# UV_Curing-PCB.net
KiCad netlist of a schematic drawn in EAGLE
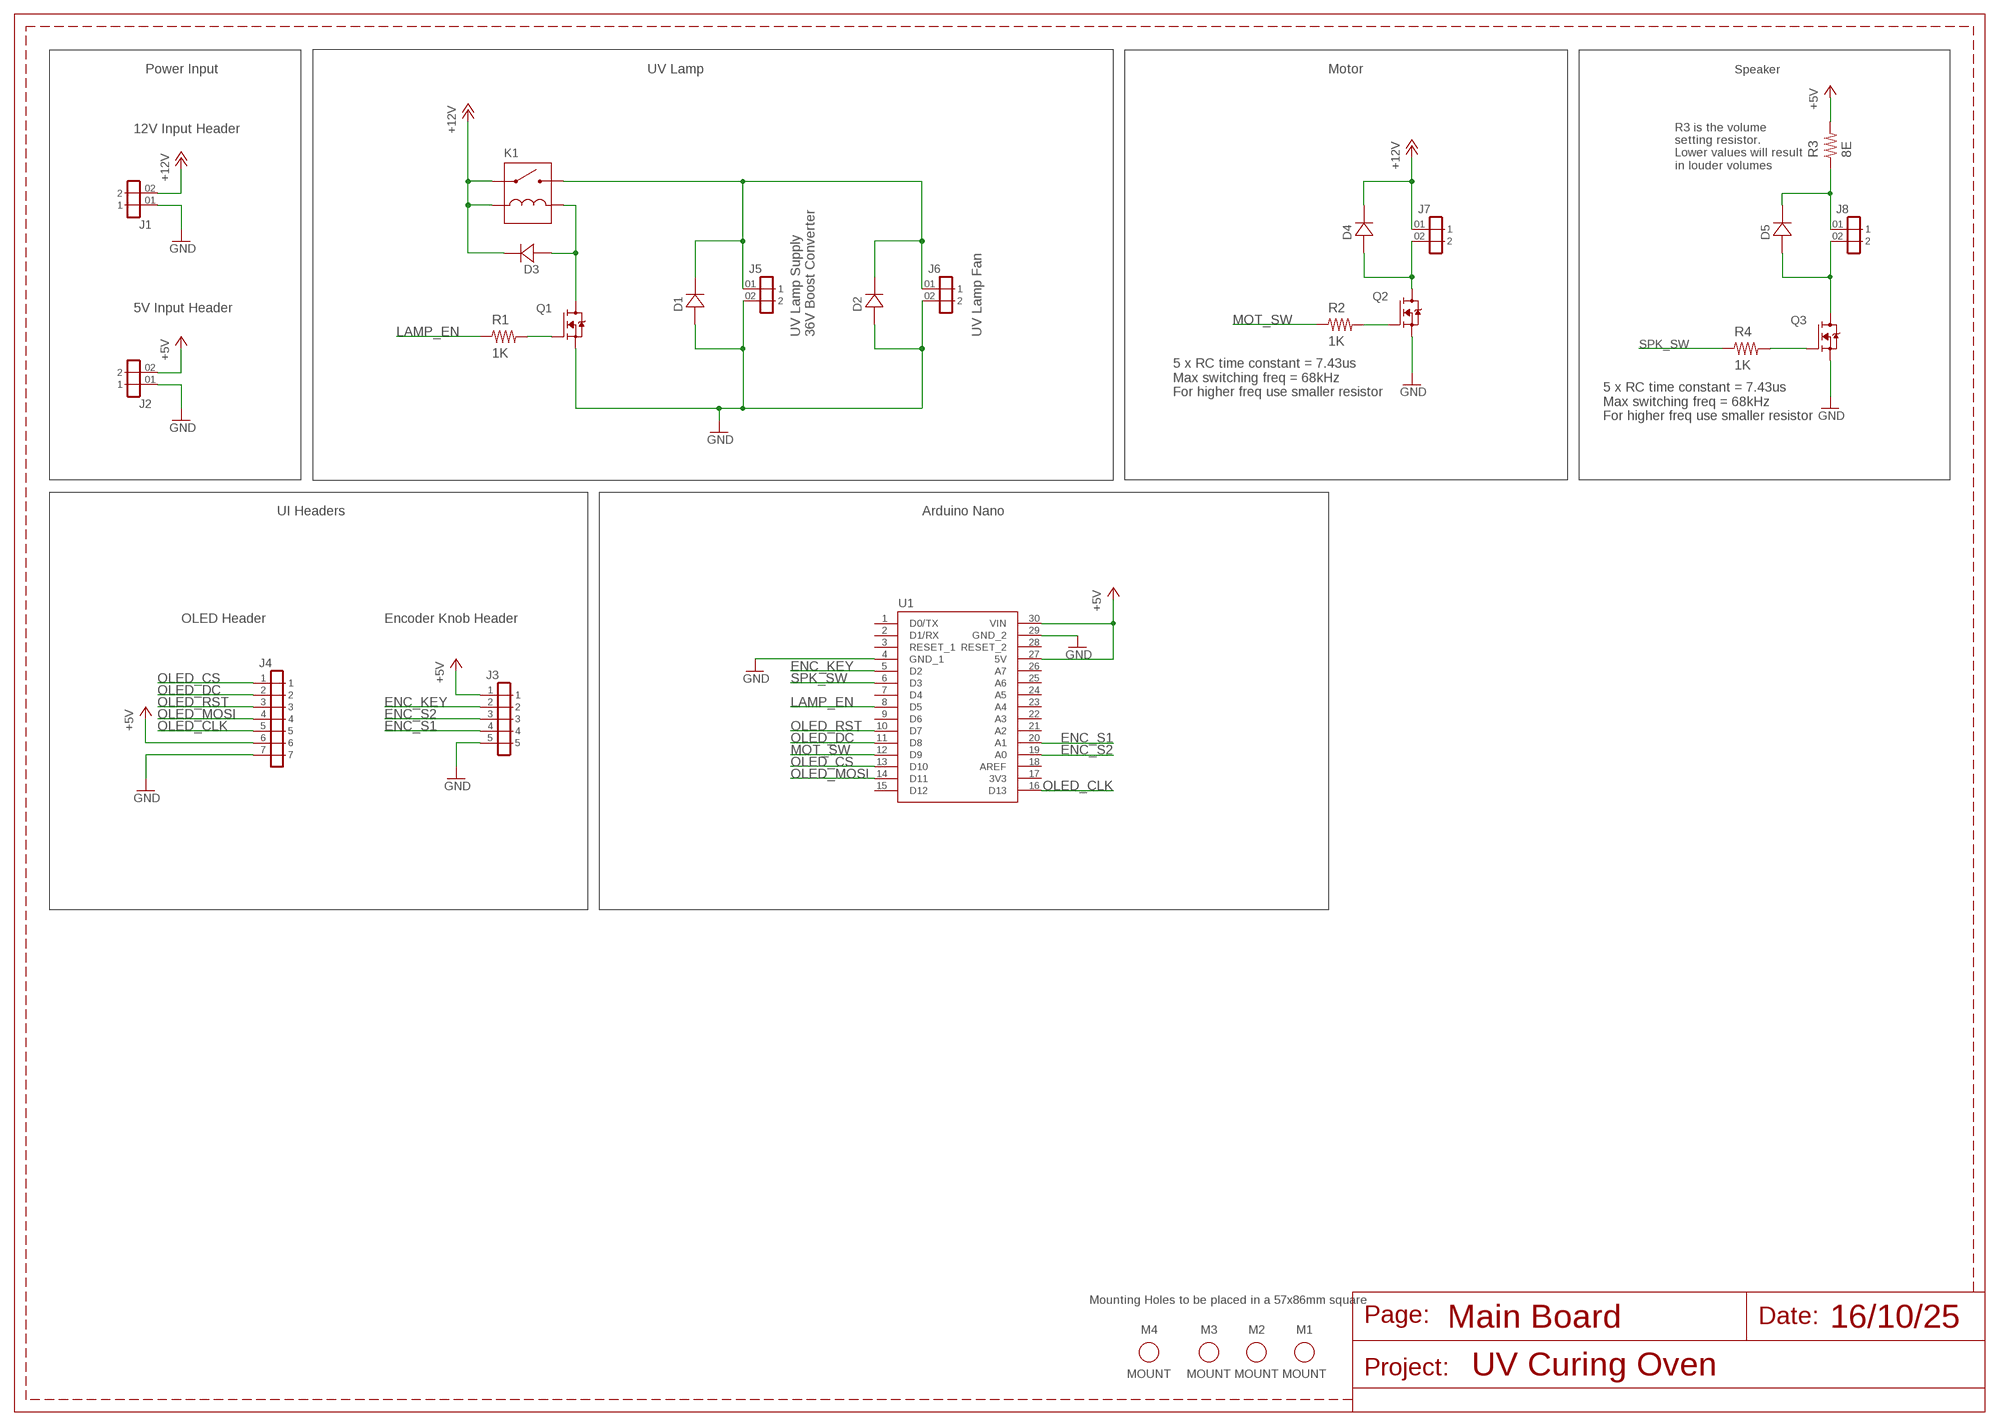
[diagram p0: schematic, sheet 1]

(export (version "E")
  (design (tool "Eeschema 10.0.6"))
  (components
    (comp (ref "D1")
      (value "400V")
      (footprint "eagle-import:DIOAD520W79L463D238")
      (fields (field (name "MF") "Diotec Semiconductor") (field (name "MP") "1N4004"))
      (libsource (lib "eagle-import") (part "DIODE-DO-41-TH"))
    )
    (comp (ref "D2")
      (value "400V")
      (footprint "eagle-import:DIOAD520W79L463D238")
      (fields (field (name "MF") "Diotec Semiconductor") (field (name "MP") "1N4004"))
      (libsource (lib "eagle-import") (part "DIODE-DO-41-TH"))
    )
    (comp (ref "D3")
      (value "400V")
      (footprint "eagle-import:DIOAD520W79L463D238")
      (fields (field (name "MF") "Diotec Semiconductor") (field (name "MP") "1N4004"))
      (libsource (lib "eagle-import") (part "DIODE-DO-41-TH"))
    )
    (comp (ref "D4")
      (value "400V")
      (footprint "eagle-import:DIOAD520W79L463D238")
      (fields (field (name "MF") "Diotec Semiconductor") (field (name "MP") "1N4004"))
      (libsource (lib "eagle-import") (part "DIODE-DO-41-TH"))
    )
    (comp (ref "D5")
      (value "400V")
      (footprint "eagle-import:DIOAD520W79L463D238")
      (fields (field (name "MF") "Diotec Semiconductor") (field (name "MP") "1N4004"))
      (libsource (lib "eagle-import") (part "DIODE-DO-41-TH"))
    )
    (comp (ref "J1")
      (value "PINHEADER-2POS-2.54MM")
      (footprint "eagle-import:254-1X02-PIN")
      (fields (field (name "MF") "Wurth Electronics") (field (name "MP") "61300211121"))
      (libsource (lib "eagle-import") (part "PINHEADER-2POS-2.54MM"))
    )
    (comp (ref "J2")
      (value "PINHEADER-2POS-2.54MM")
      (footprint "eagle-import:254-1X02-PIN")
      (fields (field (name "MF") "Wurth Electronics") (field (name "MP") "61300211121"))
      (libsource (lib "eagle-import") (part "PINHEADER-2POS-2.54MM"))
    )
    (comp (ref "J3")
      (value "PINHEADER-5POS-2.54MM")
      (footprint "eagle-import:254-1X05-PIN")
      (fields (field (name "MF") "Wurth Electronics") (field (name "MP") "61300511121"))
      (libsource (lib "eagle-import") (part "PINHEADER-5POS-2.54MM"))
    )
    (comp (ref "J4")
      (value "PINHEADER-7POS-2.54MM")
      (footprint "eagle-import:254-1X07-PIN")
      (fields (field (name "MF") "Wurth Elektronik") (field (name "MP") "61300711121"))
      (libsource (lib "eagle-import") (part "PINHEADER-7POS-2.54MM"))
    )
    (comp (ref "J5")
      (value "PINHEADER-2POS-2.54MM")
      (footprint "eagle-import:254-1X02-PIN")
      (fields (field (name "MF") "Wurth Electronics") (field (name "MP") "61300211121"))
      (libsource (lib "eagle-import") (part "PINHEADER-2POS-2.54MM"))
    )
    (comp (ref "J6")
      (value "PINHEADER-2POS-2.54MM")
      (footprint "eagle-import:254-1X02-PIN")
      (fields (field (name "MF") "Wurth Electronics") (field (name "MP") "61300211121"))
      (libsource (lib "eagle-import") (part "PINHEADER-2POS-2.54MM"))
    )
    (comp (ref "J7")
      (value "PINHEADER-2POS-2.54MM")
      (footprint "eagle-import:254-1X02-PIN")
      (fields (field (name "MF") "Wurth Electronics") (field (name "MP") "61300211121"))
      (libsource (lib "eagle-import") (part "PINHEADER-2POS-2.54MM"))
    )
    (comp (ref "J8")
      (value "PINHEADER-2POS-2.54MM")
      (footprint "eagle-import:254-1X02-PIN")
      (fields (field (name "MF") "Wurth Electronics") (field (name "MP") "61300211121"))
      (libsource (lib "eagle-import") (part "PINHEADER-2POS-2.54MM"))
    )
    (comp (ref "K1")
      (value "25V")
      (footprint "eagle-import:JY25HK505")
      (fields (field (name "MF") "FUJITSU") (field (name "MP") "JY-25H-K-505"))
      (libsource (lib "eagle-import") (part "RELAY-NO"))
    )
    (comp (ref "M1")
      (value "MOUNTING_HOLE")
      (footprint "eagle-import:M4_NP_MOUNTING_HOLE")
      (libsource (lib "eagle-import") (part "MOUNTING_HOLE"))
    )
    (comp (ref "M2")
      (value "MOUNTING_HOLE")
      (footprint "eagle-import:M4_NP_MOUNTING_HOLE")
      (libsource (lib "eagle-import") (part "MOUNTING_HOLE"))
    )
    (comp (ref "M3")
      (value "MOUNTING_HOLE")
      (footprint "eagle-import:M4_NP_MOUNTING_HOLE")
      (libsource (lib "eagle-import") (part "MOUNTING_HOLE"))
    )
    (comp (ref "M4")
      (value "MOUNTING_HOLE")
      (footprint "eagle-import:M4_NP_MOUNTING_HOLE")
      (libsource (lib "eagle-import") (part "MOUNTING_HOLE"))
    )
    (comp (ref "Q1")
      (value "55V")
      (footprint "eagle-import:TO254P1016X419X2286-3")
      (fields (field (name "MF") "Infineon") (field (name "MP") "IRFZ44NPBF"))
      (libsource (lib "eagle-import") (part "MOSFET-NCH-TO-220AB-TH"))
    )
    (comp (ref "Q2")
      (value "55V")
      (footprint "eagle-import:TO254P1016X419X2286-3")
      (fields (field (name "MF") "Infineon") (field (name "MP") "IRFZ44NPBF"))
      (libsource (lib "eagle-import") (part "MOSFET-NCH-TO-220AB-TH"))
    )
    (comp (ref "Q3")
      (value "55V")
      (footprint "eagle-import:TO254P1016X419X2286-3")
      (fields (field (name "MF") "Infineon") (field (name "MP") "IRFZ44NPBF"))
      (libsource (lib "eagle-import") (part "MOSFET-NCH-TO-220AB-TH"))
    )
    (comp (ref "R1")
      (value "1K")
      (footprint "eagle-import:RES-THRU")
      (fields (field (name "MF") "Yageo") (field (name "MP") "MFR-25FBF52-1K"))
      (libsource (lib "eagle-import") (part "MFR-25FBF52-1K"))
    )
    (comp (ref "R2")
      (value "1K")
      (footprint "eagle-import:RES-THRU")
      (fields (field (name "MF") "Yageo") (field (name "MP") "MFR-25FBF52-1K"))
      (libsource (lib "eagle-import") (part "MFR-25FBF52-1K"))
    )
    (comp (ref "R3")
      (value "8E")
      (footprint "eagle-import:RES-THRU")
      (fields (field (name "MF") "Yageo") (field (name "MP") "MFR-25FBF52-1K"))
      (libsource (lib "eagle-import") (part "MFR-25FBF52-1K"))
    )
    (comp (ref "R4")
      (value "1K")
      (footprint "eagle-import:RES-THRU")
      (fields (field (name "MF") "Yageo") (field (name "MP") "MFR-25FBF52-1K"))
      (libsource (lib "eagle-import") (part "MFR-25FBF52-1K"))
    )
    (comp (ref "U1")
      (value "A000005")
      (footprint "eagle-import:MODULE_A000005")
      (fields (field (name "MF") "Arduino"))
      (libsource (lib "eagle-import") (part "A000005"))
    )
  )
  (nets
    (net (code "1") (name "+5V") (class "Default")
      (node (ref "J2") (pin "02") (pinfunction "2_02") (pintype "passive"))
      (node (ref "J3") (pin "1") (pinfunction "1_1") (pintype "bidirectional"))
      (node (ref "J4") (pin "6") (pinfunction "6_6") (pintype "bidirectional"))
      (node (ref "R3") (pin "2") (pinfunction "2_2") (pintype "passive"))
      (node (ref "U1") (pin "27") (pinfunction "5V_27") (pintype "power_in"))
      (node (ref "U1") (pin "30") (pinfunction "VIN_30") (pintype "power_in"))
    )
    (net (code "2") (name "+12V") (class "Default")
      (node (ref "D3") (pin "C") (pinfunction "C_C") (pintype "passive"))
      (node (ref "D4") (pin "C") (pinfunction "C_C") (pintype "passive"))
      (node (ref "J1") (pin "02") (pinfunction "2_02") (pintype "passive"))
      (node (ref "J7") (pin "01") (pinfunction "1_01") (pintype "passive"))
      (node (ref "K1") (pin "16") (pinfunction "COM_16") (pintype "bidirectional"))
      (node (ref "K1") (pin "8") (pinfunction "COIL_1_8") (pintype "bidirectional"))
    )
    (net (code "3") (name "/3V3") (class "Default")
      (node (ref "U1") (pin "17") (pinfunction "3V3_17") (pintype "power_in"))
    )
    (net (code "4") (name "/ENC_KEY") (class "Default")
      (node (ref "J3") (pin "2") (pinfunction "2_2") (pintype "bidirectional"))
      (node (ref "U1") (pin "5") (pinfunction "D2_5") (pintype "bidirectional"))
    )
    (net (code "5") (name "/ENC_S1") (class "Default")
      (node (ref "J3") (pin "4") (pinfunction "4_4") (pintype "bidirectional"))
      (node (ref "U1") (pin "20") (pinfunction "A1_20") (pintype "input"))
    )
    (net (code "6") (name "/ENC_S2") (class "Default")
      (node (ref "J3") (pin "3") (pinfunction "3_3") (pintype "bidirectional"))
      (node (ref "U1") (pin "19") (pinfunction "A0_19") (pintype "input"))
    )
    (net (code "7") (name "/LAMP_EN") (class "Default")
      (node (ref "R1") (pin "1") (pinfunction "1_1") (pintype "passive"))
      (node (ref "U1") (pin "8") (pinfunction "D5_8") (pintype "bidirectional"))
    )
    (net (code "8") (name "/MOT_SW") (class "Default")
      (node (ref "R2") (pin "1") (pinfunction "1_1") (pintype "passive"))
      (node (ref "U1") (pin "12") (pinfunction "D9_12") (pintype "bidirectional"))
    )
    (net (code "9") (name "/OLED_CLK") (class "Default")
      (node (ref "J4") (pin "5") (pinfunction "5_5") (pintype "bidirectional"))
      (node (ref "U1") (pin "16") (pinfunction "D13_16") (pintype "bidirectional"))
    )
    (net (code "10") (name "/OLED_CS") (class "Default")
      (node (ref "J4") (pin "1") (pinfunction "1_1") (pintype "bidirectional"))
      (node (ref "U1") (pin "13") (pinfunction "D10_13") (pintype "bidirectional"))
    )
    (net (code "11") (name "/OLED_DC") (class "Default")
      (node (ref "J4") (pin "2") (pinfunction "2_2") (pintype "bidirectional"))
      (node (ref "U1") (pin "11") (pinfunction "D8_11") (pintype "bidirectional"))
    )
    (net (code "12") (name "/OLED_MOSI") (class "Default")
      (node (ref "J4") (pin "4") (pinfunction "4_4") (pintype "bidirectional"))
      (node (ref "U1") (pin "14") (pinfunction "D11_14") (pintype "bidirectional"))
    )
    (net (code "13") (name "/OLED_RST") (class "Default")
      (node (ref "J4") (pin "3") (pinfunction "3_3") (pintype "bidirectional"))
      (node (ref "U1") (pin "10") (pinfunction "D7_10") (pintype "bidirectional"))
    )
    (net (code "14") (name "/SPK_SW") (class "Default")
      (node (ref "R4") (pin "1") (pinfunction "1_1") (pintype "passive"))
      (node (ref "U1") (pin "6") (pinfunction "D3_6") (pintype "bidirectional"))
    )
    (net (code "15") (name "GND") (class "Default")
      (node (ref "D1") (pin "A") (pinfunction "A_A") (pintype "passive"))
      (node (ref "D2") (pin "A") (pinfunction "A_A") (pintype "passive"))
      (node (ref "J1") (pin "01") (pinfunction "1_01") (pintype "passive"))
      (node (ref "J2") (pin "01") (pinfunction "1_01") (pintype "passive"))
      (node (ref "J3") (pin "5") (pinfunction "5_5") (pintype "bidirectional"))
      (node (ref "J4") (pin "7") (pinfunction "7_7") (pintype "bidirectional"))
      (node (ref "J5") (pin "02") (pinfunction "2_02") (pintype "passive"))
      (node (ref "J6") (pin "02") (pinfunction "2_02") (pintype "passive"))
      (node (ref "Q1") (pin "3") (pinfunction "S_3") (pintype "passive"))
      (node (ref "Q2") (pin "3") (pinfunction "S_3") (pintype "passive"))
      (node (ref "Q3") (pin "3") (pinfunction "S_3") (pintype "passive"))
      (node (ref "U1") (pin "29") (pinfunction "GND_2_29") (pintype "power_in"))
      (node (ref "U1") (pin "4") (pinfunction "GND_1_4") (pintype "power_in"))
    )
    (net (code "16") (name "Net-(J5-1)") (class "Default")
      (node (ref "D1") (pin "C") (pinfunction "C_C") (pintype "passive"))
      (node (ref "D2") (pin "C") (pinfunction "C_C") (pintype "passive"))
      (node (ref "J5") (pin "01") (pinfunction "1_01") (pintype "passive"))
      (node (ref "J6") (pin "01") (pinfunction "1_01") (pintype "passive"))
      (node (ref "K1") (pin "13") (pinfunction "NO_13") (pintype "bidirectional"))
    )
    (net (code "17") (name "Net-(J7-2)") (class "Default")
      (node (ref "D4") (pin "A") (pinfunction "A_A") (pintype "passive"))
      (node (ref "J7") (pin "02") (pinfunction "2_02") (pintype "passive"))
      (node (ref "Q2") (pin "2") (pinfunction "D_2") (pintype "passive"))
    )
    (net (code "18") (name "Net-(J8-1)") (class "Default")
      (node (ref "D5") (pin "C") (pinfunction "C_C") (pintype "passive"))
      (node (ref "J8") (pin "01") (pinfunction "1_01") (pintype "passive"))
      (node (ref "R3") (pin "1") (pinfunction "1_1") (pintype "passive"))
    )
    (net (code "19") (name "Net-(J8-2)") (class "Default")
      (node (ref "D5") (pin "A") (pinfunction "A_A") (pintype "passive"))
      (node (ref "J8") (pin "02") (pinfunction "2_02") (pintype "passive"))
      (node (ref "Q3") (pin "2") (pinfunction "D_2") (pintype "passive"))
    )
    (net (code "20") (name "Net-(K1-COIL_2)") (class "Default")
      (node (ref "D3") (pin "A") (pinfunction "A_A") (pintype "passive"))
      (node (ref "K1") (pin "9") (pinfunction "COIL_2_9") (pintype "bidirectional"))
      (node (ref "Q1") (pin "2") (pinfunction "D_2") (pintype "passive"))
    )
    (net (code "21") (name "Net-(Q1-G)") (class "Default")
      (node (ref "Q1") (pin "1") (pinfunction "G_1") (pintype "passive"))
      (node (ref "R1") (pin "2") (pinfunction "2_2") (pintype "passive"))
    )
    (net (code "22") (name "Net-(Q2-G)") (class "Default")
      (node (ref "Q2") (pin "1") (pinfunction "G_1") (pintype "passive"))
      (node (ref "R2") (pin "2") (pinfunction "2_2") (pintype "passive"))
    )
    (net (code "23") (name "Net-(Q3-G)") (class "Default")
      (node (ref "Q3") (pin "1") (pinfunction "G_1") (pintype "passive"))
      (node (ref "R4") (pin "2") (pinfunction "2_2") (pintype "passive"))
    )
    (net (code "24") (name "unconnected-(U1-A2-Pad21)") (class "Default")
      (node (ref "U1") (pin "21") (pinfunction "A2_21") (pintype "input"))
    )
    (net (code "25") (name "unconnected-(U1-A3-Pad22)") (class "Default")
      (node (ref "U1") (pin "22") (pinfunction "A3_22") (pintype "input"))
    )
    (net (code "26") (name "unconnected-(U1-A4-Pad23)") (class "Default")
      (node (ref "U1") (pin "23") (pinfunction "A4_23") (pintype "input"))
    )
    (net (code "27") (name "unconnected-(U1-A5-Pad24)") (class "Default")
      (node (ref "U1") (pin "24") (pinfunction "A5_24") (pintype "input"))
    )
    (net (code "28") (name "unconnected-(U1-A6-Pad25)") (class "Default")
      (node (ref "U1") (pin "25") (pinfunction "A6_25") (pintype "input"))
    )
    (net (code "29") (name "unconnected-(U1-A7-Pad26)") (class "Default")
      (node (ref "U1") (pin "26") (pinfunction "A7_26") (pintype "input"))
    )
    (net (code "30") (name "unconnected-(U1-AREF-Pad18)") (class "Default")
      (node (ref "U1") (pin "18") (pinfunction "AREF_18") (pintype "input"))
    )
    (net (code "31") (name "unconnected-(U1-D0{slash}TX-Pad1)") (class "Default")
      (node (ref "U1") (pin "1") (pinfunction "D0/TX_1") (pintype "bidirectional"))
    )
    (net (code "32") (name "unconnected-(U1-D1{slash}RX-Pad2)") (class "Default")
      (node (ref "U1") (pin "2") (pinfunction "D1/RX_2") (pintype "bidirectional"))
    )
    (net (code "33") (name "unconnected-(U1-D4-Pad7)") (class "Default")
      (node (ref "U1") (pin "7") (pinfunction "D4_7") (pintype "bidirectional"))
    )
    (net (code "34") (name "unconnected-(U1-D6-Pad9)") (class "Default")
      (node (ref "U1") (pin "9") (pinfunction "D6_9") (pintype "bidirectional"))
    )
    (net (code "35") (name "unconnected-(U1-D12-Pad15)") (class "Default")
      (node (ref "U1") (pin "15") (pinfunction "D12_15") (pintype "bidirectional"))
    )
    (net (code "36") (name "unconnected-(U1-RESET_1-Pad3)") (class "Default")
      (node (ref "U1") (pin "3") (pinfunction "RESET_1_3") (pintype "input"))
    )
    (net (code "37") (name "unconnected-(U1-RESET_2-Pad28)") (class "Default")
      (node (ref "U1") (pin "28") (pinfunction "RESET_2_28") (pintype "input"))
    )
  )
)
